# ESP8266_uS_board.net
KiCad netlist of a schematic drawn in EAGLE
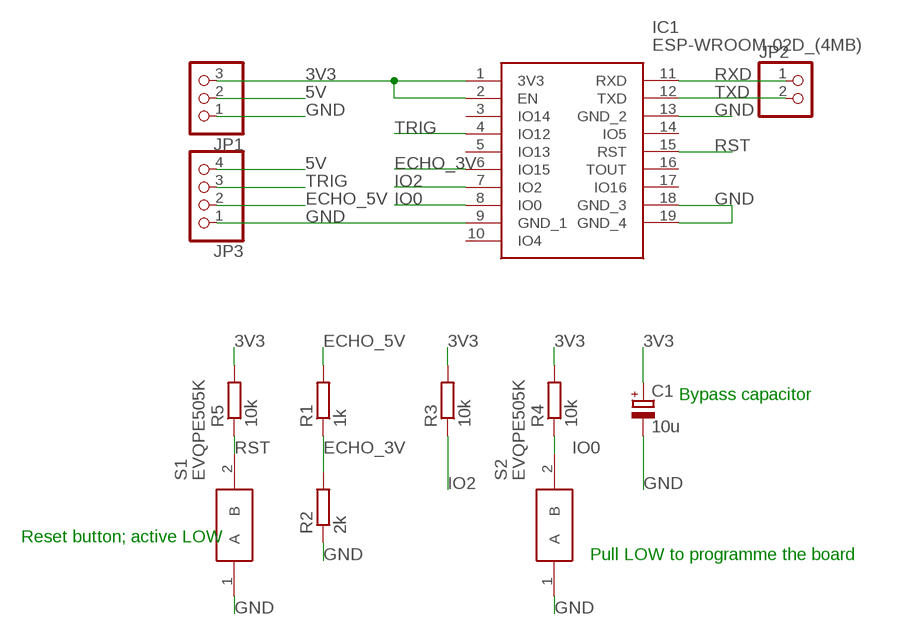
[diagram p0: schematic, sheet 1]

(export (version "E")
  (design (tool "Eeschema 10.0.6"))
  (components
    (comp (ref "C1")
      (value "10u")
      (footprint "eagle-import:D_7343-31R")
      (libsource (lib "eagle-import") (part "CPOL-EUD/7343-31R"))
    )
    (comp (ref "IC1")
      (value "ESP-WROOM-02D_(4MB)")
      (footprint "eagle-import:ESPWROOM02D")
      (fields
        (field (name "MANUFACTURER_PART_NUMBER") "ESP-WROOM-02D (4MB)")
        (field (name "MOUSER_PART_NUMBER") "356-ESPWROOM02D(4MB)")
      )
      (libsource (lib "eagle-import") (part "ESP-WROOM-02D_(4MB)"))
    )
    (comp (ref "JP1")
      (value "PINHD-1X3")
      (footprint "eagle-import:1X03")
      (libsource (lib "eagle-import") (part "PINHD-1X3"))
    )
    (comp (ref "JP2")
      (value "PINHD-1X2")
      (footprint "eagle-import:1X02")
      (libsource (lib "eagle-import") (part "PINHD-1X2"))
    )
    (comp (ref "JP3")
      (value "PINHD-1X4")
      (footprint "eagle-import:1X04")
      (libsource (lib "eagle-import") (part "PINHD-1X4"))
    )
    (comp (ref "R1")
      (value "1k")
      (footprint "eagle-import:R0805")
      (libsource (lib "eagle-import") (part "R-EU_R0805"))
    )
    (comp (ref "R2")
      (value "2k")
      (footprint "eagle-import:R0805")
      (libsource (lib "eagle-import") (part "R-EU_R0805"))
    )
    (comp (ref "R3")
      (value "10k")
      (footprint "eagle-import:R0805")
      (libsource (lib "eagle-import") (part "R-EU_R0805"))
    )
    (comp (ref "R4")
      (value "10k")
      (footprint "eagle-import:R0805")
      (libsource (lib "eagle-import") (part "R-EU_R0805"))
    )
    (comp (ref "R5")
      (value "10k")
      (footprint "eagle-import:R0805")
      (libsource (lib "eagle-import") (part "R-EU_R0805"))
    )
    (comp (ref "S1")
      (value "EVQPE505K")
      (footprint "eagle-import:EVQPE505K")
      (fields (field (name "RS_PART_NUMBER") "7561565P"))
      (libsource (lib "eagle-import") (part "EVQPE505K"))
    )
    (comp (ref "S2")
      (value "EVQPE505K")
      (footprint "eagle-import:EVQPE505K")
      (fields (field (name "RS_PART_NUMBER") "7561565P"))
      (libsource (lib "eagle-import") (part "EVQPE505K"))
    )
  )
  (nets
    (net (code "1") (name "/3V3") (class "Default")
      (node (ref "C1") (pin "+") (pinfunction "+_+") (pintype "passive"))
      (node (ref "IC1") (pin "1") (pinfunction "3V3_1") (pintype "bidirectional"))
      (node (ref "IC1") (pin "2") (pinfunction "EN_2") (pintype "bidirectional"))
      (node (ref "JP1") (pin "3") (pinfunction "3_3") (pintype "passive"))
      (node (ref "R3") (pin "2") (pinfunction "2_2") (pintype "passive"))
      (node (ref "R4") (pin "2") (pinfunction "2_2") (pintype "passive"))
      (node (ref "R5") (pin "2") (pinfunction "2_2") (pintype "passive"))
    )
    (net (code "2") (name "/5V") (class "Default")
      (node (ref "JP1") (pin "2") (pinfunction "2_2") (pintype "passive"))
      (node (ref "JP3") (pin "4") (pinfunction "4_4") (pintype "passive"))
    )
    (net (code "3") (name "/ECHO_3V") (class "Default")
      (node (ref "IC1") (pin "6") (pinfunction "IO15_6") (pintype "bidirectional"))
      (node (ref "R1") (pin "1") (pinfunction "1_1") (pintype "passive"))
      (node (ref "R2") (pin "2") (pinfunction "2_2") (pintype "passive"))
    )
    (net (code "4") (name "/ECHO_5V") (class "Default")
      (node (ref "JP3") (pin "2") (pinfunction "2_2") (pintype "passive"))
      (node (ref "R1") (pin "2") (pinfunction "2_2") (pintype "passive"))
    )
    (net (code "5") (name "/GND") (class "Default")
      (node (ref "C1") (pin "-") (pinfunction "-_-") (pintype "passive"))
      (node (ref "IC1") (pin "13") (pinfunction "GND_2_13") (pintype "bidirectional"))
      (node (ref "IC1") (pin "18") (pinfunction "GND_3_18") (pintype "bidirectional"))
      (node (ref "IC1") (pin "19") (pinfunction "GND_4_19") (pintype "bidirectional"))
      (node (ref "IC1") (pin "9") (pinfunction "GND_1_9") (pintype "bidirectional"))
      (node (ref "JP1") (pin "1") (pinfunction "1_1") (pintype "passive"))
      (node (ref "JP3") (pin "1") (pinfunction "1_1") (pintype "passive"))
      (node (ref "R2") (pin "1") (pinfunction "1_1") (pintype "passive"))
      (node (ref "S1") (pin "1") (pinfunction "A_1") (pintype "bidirectional"))
      (node (ref "S2") (pin "1") (pinfunction "A_1") (pintype "bidirectional"))
    )
    (net (code "6") (name "/IO0") (class "Default")
      (node (ref "IC1") (pin "8") (pinfunction "IO0_8") (pintype "bidirectional"))
      (node (ref "R4") (pin "1") (pinfunction "1_1") (pintype "passive"))
      (node (ref "S2") (pin "2") (pinfunction "B_2") (pintype "bidirectional"))
    )
    (net (code "7") (name "/IO2") (class "Default")
      (node (ref "IC1") (pin "7") (pinfunction "IO2_7") (pintype "bidirectional"))
      (node (ref "R3") (pin "1") (pinfunction "1_1") (pintype "passive"))
    )
    (net (code "8") (name "/RST") (class "Default")
      (node (ref "IC1") (pin "15") (pinfunction "RST_15") (pintype "bidirectional"))
      (node (ref "R5") (pin "1") (pinfunction "1_1") (pintype "passive"))
      (node (ref "S1") (pin "2") (pinfunction "B_2") (pintype "bidirectional"))
    )
    (net (code "9") (name "/RXD") (class "Default")
      (node (ref "IC1") (pin "11") (pinfunction "RXD_11") (pintype "bidirectional"))
      (node (ref "JP2") (pin "1") (pinfunction "1_1") (pintype "passive"))
    )
    (net (code "10") (name "/TRIG") (class "Default")
      (node (ref "IC1") (pin "4") (pinfunction "IO12_4") (pintype "bidirectional"))
      (node (ref "JP3") (pin "3") (pinfunction "3_3") (pintype "passive"))
    )
    (net (code "11") (name "/TXD") (class "Default")
      (node (ref "IC1") (pin "12") (pinfunction "TXD_12") (pintype "bidirectional"))
      (node (ref "JP2") (pin "2") (pinfunction "2_2") (pintype "passive"))
    )
    (net (code "12") (name "unconnected-(IC1-IO4-Pad10)") (class "Default")
      (node (ref "IC1") (pin "10") (pinfunction "IO4_10") (pintype "bidirectional"))
    )
    (net (code "13") (name "unconnected-(IC1-IO5-Pad14)") (class "Default")
      (node (ref "IC1") (pin "14") (pinfunction "IO5_14") (pintype "bidirectional"))
    )
    (net (code "14") (name "unconnected-(IC1-IO13-Pad5)") (class "Default")
      (node (ref "IC1") (pin "5") (pinfunction "IO13_5") (pintype "bidirectional"))
    )
    (net (code "15") (name "unconnected-(IC1-IO14-Pad3)") (class "Default")
      (node (ref "IC1") (pin "3") (pinfunction "IO14_3") (pintype "bidirectional"))
    )
    (net (code "16") (name "unconnected-(IC1-IO16-Pad17)") (class "Default")
      (node (ref "IC1") (pin "17") (pinfunction "IO16_17") (pintype "bidirectional"))
    )
    (net (code "17") (name "unconnected-(IC1-TOUT-Pad16)") (class "Default")
      (node (ref "IC1") (pin "16") (pinfunction "TOUT_16") (pintype "bidirectional"))
    )
  )
)
